# Laboratoire2_MemRTC-I2C-ETU.net
KiCad netlist of a schematic drawn in Altium Designer
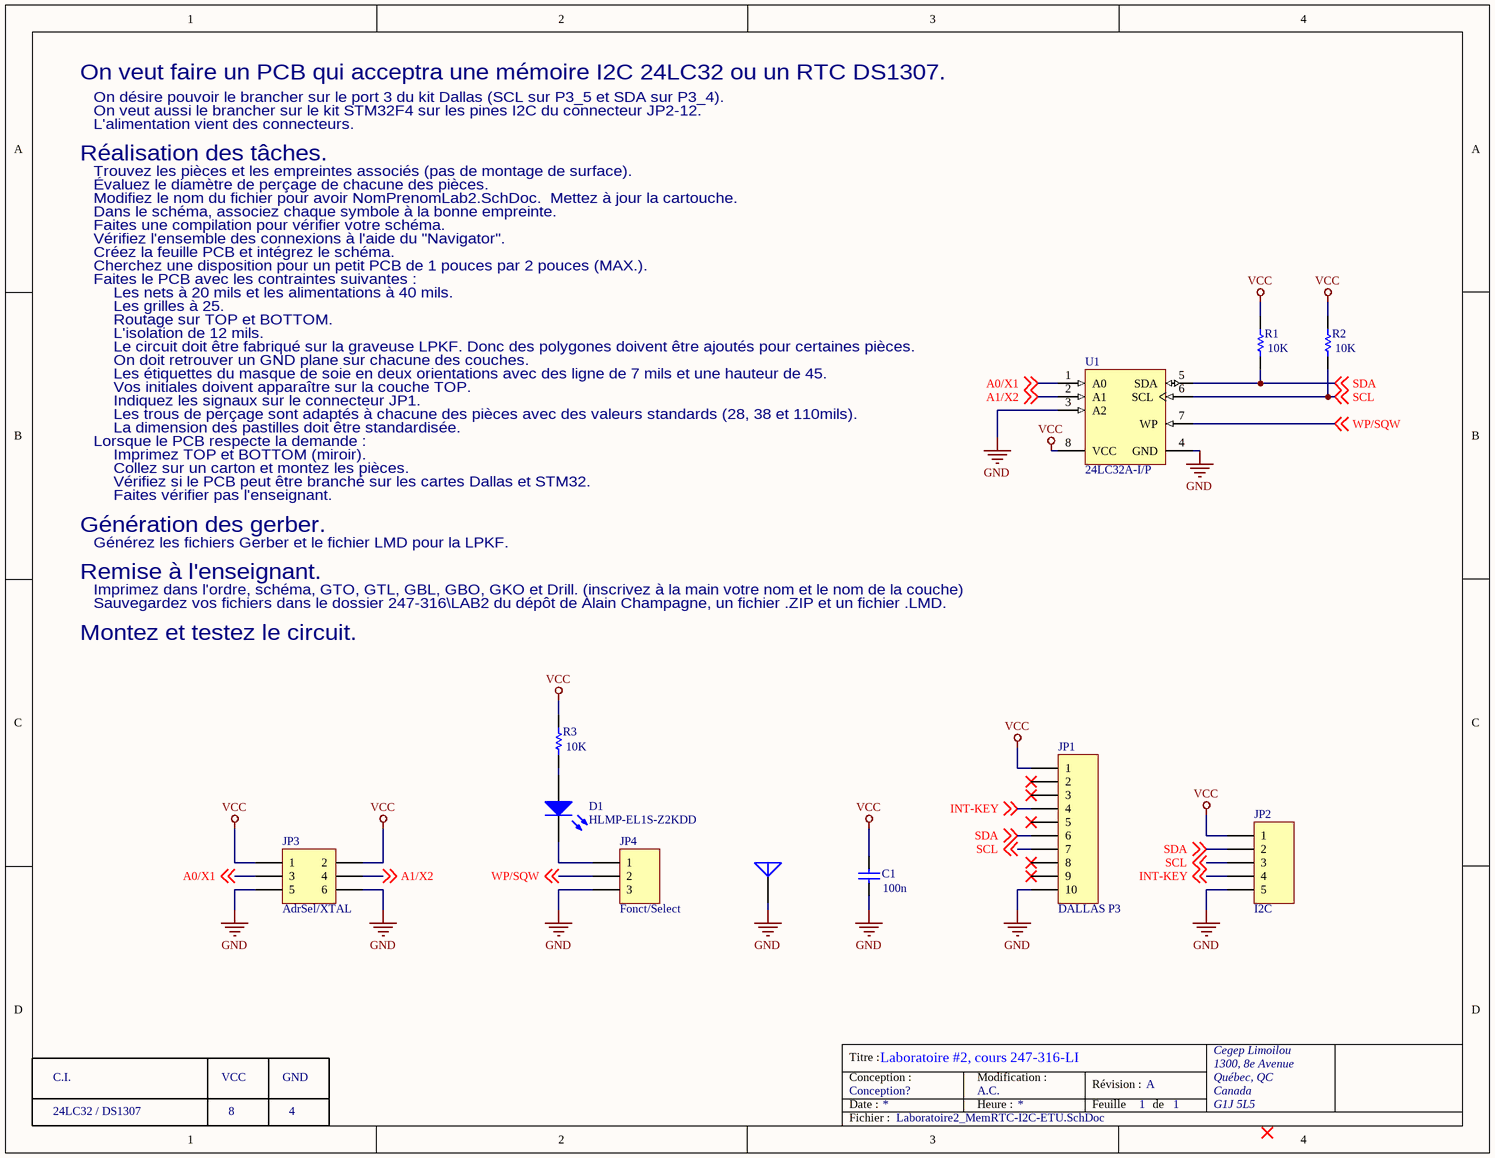
[diagram p0: Laboratoire2_MemRTC-I2C-ETU.SchDoc]

(export (version "E")
  (design (tool "Eeschema 10.0.6"))
  (components
    (comp (ref "C1")
      (value "100n")
      (footprint "AC100\\125_2")
      (description "Capacitor")
      (fields (field (name "PUBLISHER") "Altium Limited"))
      (libsource (lib "Miscellaneous Devices") (part "Cap"))
    )
    (comp (ref "D1")
      (value "HLMP-EL1S-Z2KDD")
      (footprint "RC100\\200+_2")
      (description "Typical INFRARED GaAs LED")
      (fields (field (name "PUBLISHER") "Altium Limited"))
      (libsource (lib "Miscellaneous Devices") (part "LED0"))
    )
    (comp (ref "JP1")
      (value "DALLAS P3")
      (footprint "SIP\\10P_2")
      (description "Header, 10-Pin")
      (fields (field (name "PUBLISHER") "Altium Limited"))
      (libsource (lib "Miscellaneous Connectors") (part "Header 10"))
    )
    (comp (ref "JP2")
      (value "I2C")
      (footprint "MOLEX5_2")
      (description "Header, 5-Pin")
      (fields (field (name "PUBLISHER") "Altium Limited"))
      (libsource (lib "Miscellaneous Connectors") (part "Header 5"))
    )
    (comp (ref "JP3")
      (value "AdrSel/XTAL")
      (footprint "J\\6P_2")
      (description "Header, 3-Pin, Dual row")
      (fields (field (name "PUBLISHER") "Altium Limited"))
      (libsource (lib "Miscellaneous Connectors") (part "Header 3X2"))
    )
    (comp (ref "JP4")
      (value "Fonct/Select")
      (footprint "SIP\\3P_2")
      (description "Header, 3-Pin")
      (fields (field (name "PUBLISHER") "Altium Limited"))
      (libsource (lib "Miscellaneous Connectors") (part "Header 3"))
    )
    (comp (ref "MTH1")
      (value "Montage")
      (footprint "MTHOLE1")
      (description "Generic Antenna")
      (fields (field (name "PUBLISHER") "Altium Limited"))
      (libsource (lib "Miscellaneous Devices") (part "Antenna"))
    )
    (comp (ref "R1")
      (value "10K")
      (footprint "R400_2")
      (description "Resistor")
      (fields (field (name "PUBLISHER") "Altium Limited"))
      (libsource (lib "Miscellaneous Devices") (part "Res1"))
    )
    (comp (ref "R2")
      (value "10K")
      (footprint "R400_2")
      (description "Resistor")
      (fields (field (name "PUBLISHER") "Altium Limited"))
      (libsource (lib "Miscellaneous Devices") (part "Res1"))
    )
    (comp (ref "R3")
      (value "10K")
      (footprint "R400_2")
      (description "Resistor")
      (fields (field (name "PUBLISHER") "Altium Limited"))
      (libsource (lib "Miscellaneous Devices") (part "Res1"))
    )
    (comp (ref "U1")
      (value "24LC32A-I/P")
      (footprint "DIP8_2")
      (description "32Kbit, 400kHz, 2.5V, I2C Serial EEPROM, 8-Pin PDIP, Industrial Temperature")
      (fields (field (name "PUBLISHER") "Altium Limited"))
      (libsource (lib "MemRTC-I2C") (part "24LC32A-I/P"))
    )
  )
  (nets
    (net (code "1") (name "A0{slash}X1") (class "Default")
      (node (ref "JP3") (pin "3") (pinfunction "3_3") (pintype "passive"))
      (node (ref "U1") (pin "1") (pinfunction "A0_1") (pintype "input"))
    )
    (net (code "2") (name "A1{slash}X2") (class "Default")
      (node (ref "JP3") (pin "4") (pinfunction "4_4") (pintype "passive"))
      (node (ref "U1") (pin "2") (pinfunction "A1_2") (pintype "input"))
    )
    (net (code "3") (name "GND") (class "Default")
      (node (ref "C1") (pin "1") (pinfunction "1_1") (pintype "passive"))
      (node (ref "JP1") (pin "10") (pinfunction "10_10") (pintype "passive"))
      (node (ref "JP2") (pin "5") (pinfunction "5_5") (pintype "passive"))
      (node (ref "JP3") (pin "5") (pinfunction "5_5") (pintype "passive"))
      (node (ref "JP3") (pin "6") (pinfunction "6_6") (pintype "passive"))
      (node (ref "JP4") (pin "3") (pinfunction "3_3") (pintype "passive"))
      (node (ref "MTH1") (pin "1") (pinfunction "A_1") (pintype "passive"))
      (node (ref "U1") (pin "3") (pinfunction "A2_3") (pintype "input"))
      (node (ref "U1") (pin "4") (pinfunction "GND_4") (pintype "power_in"))
    )
    (net (code "4") (name "INT-KEY") (class "Default")
      (node (ref "JP1") (pin "4") (pinfunction "4_4") (pintype "passive"))
      (node (ref "JP2") (pin "4") (pinfunction "4_4") (pintype "passive"))
    )
    (net (code "5") (name "Net-(D1-A)") (class "Default")
      (node (ref "D1") (pin "1") (pinfunction "A_1") (pintype "passive"))
      (node (ref "R3") (pin "1") (pinfunction "1_1") (pintype "passive"))
    )
    (net (code "6") (name "Net-(D1-K)") (class "Default")
      (node (ref "D1") (pin "2") (pinfunction "K_2") (pintype "passive"))
      (node (ref "JP4") (pin "1") (pinfunction "1_1") (pintype "passive"))
    )
    (net (code "7") (name "SCL") (class "Default")
      (node (ref "JP1") (pin "7") (pinfunction "7_7") (pintype "passive"))
      (node (ref "JP2") (pin "3") (pinfunction "3_3") (pintype "passive"))
      (node (ref "R2") (pin "1") (pinfunction "1_1") (pintype "passive"))
      (node (ref "U1") (pin "6") (pinfunction "SCL_6") (pintype "input"))
    )
    (net (code "8") (name "SDA") (class "Default")
      (node (ref "JP1") (pin "6") (pinfunction "6_6") (pintype "passive"))
      (node (ref "JP2") (pin "2") (pinfunction "2_2") (pintype "passive"))
      (node (ref "R1") (pin "1") (pinfunction "1_1") (pintype "passive"))
      (node (ref "U1") (pin "5") (pinfunction "SDA_5") (pintype "bidirectional"))
    )
    (net (code "9") (name "VCC") (class "Default")
      (node (ref "C1") (pin "2") (pinfunction "2_2") (pintype "passive"))
      (node (ref "JP1") (pin "1") (pinfunction "1_1") (pintype "passive"))
      (node (ref "JP2") (pin "1") (pinfunction "1_1") (pintype "passive"))
      (node (ref "JP3") (pin "1") (pinfunction "1_1") (pintype "passive"))
      (node (ref "JP3") (pin "2") (pinfunction "2_2") (pintype "passive"))
      (node (ref "R1") (pin "2") (pinfunction "2_2") (pintype "passive"))
      (node (ref "R2") (pin "2") (pinfunction "2_2") (pintype "passive"))
      (node (ref "R3") (pin "2") (pinfunction "2_2") (pintype "passive"))
      (node (ref "U1") (pin "8") (pinfunction "VCC_8") (pintype "power_in"))
    )
    (net (code "10") (name "WP{slash}SQW") (class "Default")
      (node (ref "JP4") (pin "2") (pinfunction "2_2") (pintype "passive"))
      (node (ref "U1") (pin "7") (pinfunction "WP_7") (pintype "input"))
    )
    (net (code "11") (name "unconnected-(JP1-Pad2)") (class "Default")
      (node (ref "JP1") (pin "2") (pinfunction "2_2") (pintype "passive+no_connect"))
    )
    (net (code "12") (name "unconnected-(JP1-Pad3)") (class "Default")
      (node (ref "JP1") (pin "3") (pinfunction "3_3") (pintype "passive+no_connect"))
    )
    (net (code "13") (name "unconnected-(JP1-Pad5)") (class "Default")
      (node (ref "JP1") (pin "5") (pinfunction "5_5") (pintype "passive+no_connect"))
    )
    (net (code "14") (name "unconnected-(JP1-Pad8)") (class "Default")
      (node (ref "JP1") (pin "8") (pinfunction "8_8") (pintype "passive+no_connect"))
    )
    (net (code "15") (name "unconnected-(JP1-Pad9)") (class "Default")
      (node (ref "JP1") (pin "9") (pinfunction "9_9") (pintype "passive+no_connect"))
    )
  )
)
